# dummy.net
KiCad netlist of a schematic drawn in EAGLE
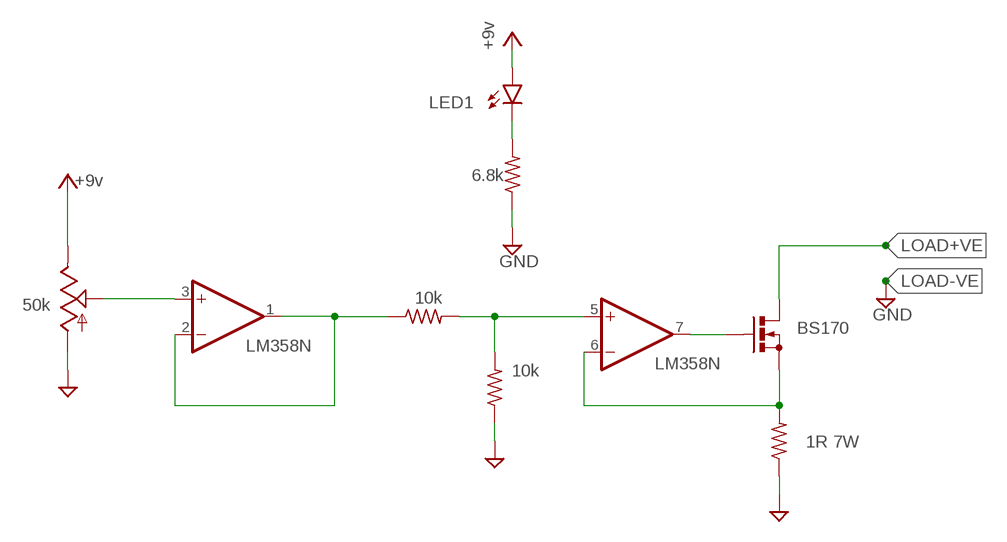
[diagram p0: schematic, sheet 1]

(export (version "E")
  (design (tool "Eeschema 10.0.6"))
  (components
    (comp (ref "IC1")
      (value "LM358N")
      (footprint "eagle-import:DIL08")
      (libsource (lib "eagle-import") (part "LM358N"))
    )
    (comp (ref "LED1")
      (value "LED5MM")
      (footprint "eagle-import:LED5MM")
      (libsource (lib "eagle-import") (part "LED5MM"))
    )
    (comp (ref "Q1")
      (value "BS170")
      (footprint "eagle-import:SOT54E")
      (libsource (lib "eagle-import") (part "BS170"))
    )
    (comp (ref "R1")
      (value "50k")
      (footprint "eagle-import:B25P")
      (libsource (lib "eagle-import") (part "TRIM_US-B25P"))
    )
    (comp (ref "R2")
      (value "10k")
      (footprint "eagle-import:0207_10")
      (libsource (lib "eagle-import") (part "R-US_0207/10"))
    )
    (comp (ref "R3")
      (value "10k")
      (footprint "eagle-import:0207_10")
      (libsource (lib "eagle-import") (part "R-US_0207/10"))
    )
    (comp (ref "R4")
      (value "1R 7W")
      (footprint "eagle-import:0207_10")
      (libsource (lib "eagle-import") (part "R-US_0207/10"))
    )
    (comp (ref "R5")
      (value "6.8k")
      (footprint "eagle-import:0207_10")
      (libsource (lib "eagle-import") (part "R-US_0207/10"))
    )
  )
  (nets
    (net (code "1") (name "+9v") (class "Default")
      (node (ref "LED1") (pin "A") (pinfunction "A_A") (pintype "passive"))
      (node (ref "R1") (pin "E") (pinfunction "E_E") (pintype "passive"))
    )
    (net (code "2") (name "LOAD+VE") (class "Default")
      (node (ref "Q1") (pin "D") (pinfunction "D_D") (pintype "passive"))
    )
    (net (code "3") (name "LOAD-VE") (class "Default")
      (node (ref "R1") (pin "A") (pinfunction "A_A") (pintype "passive"))
      (node (ref "R3") (pin "1") (pinfunction "1_1") (pintype "passive"))
      (node (ref "R4") (pin "1") (pinfunction "1_1") (pintype "passive"))
      (node (ref "R5") (pin "1") (pinfunction "1_1") (pintype "passive"))
    )
    (net (code "4") (name "Net-(IC1A-+IN)") (class "Default")
      (node (ref "IC1") (pin "3") (pinfunction "+IN_3") (pintype "input"))
      (node (ref "R1") (pin "S") (pinfunction "S_S") (pintype "passive"))
    )
    (net (code "5") (name "Net-(IC1A--IN)") (class "Default")
      (node (ref "IC1") (pin "1") (pinfunction "OUT_1") (pintype "output"))
      (node (ref "IC1") (pin "2") (pinfunction "-IN_2") (pintype "input"))
      (node (ref "R2") (pin "1") (pinfunction "1_1") (pintype "passive"))
    )
    (net (code "6") (name "Net-(IC1B-+IN)") (class "Default")
      (node (ref "IC1") (pin "5") (pinfunction "+IN_5") (pintype "input"))
      (node (ref "R2") (pin "2") (pinfunction "2_2") (pintype "passive"))
      (node (ref "R3") (pin "2") (pinfunction "2_2") (pintype "passive"))
    )
    (net (code "7") (name "Net-(IC1B--IN)") (class "Default")
      (node (ref "IC1") (pin "6") (pinfunction "-IN_6") (pintype "input"))
      (node (ref "Q1") (pin "S") (pinfunction "S_S") (pintype "passive"))
      (node (ref "R4") (pin "2") (pinfunction "2_2") (pintype "passive"))
    )
    (net (code "8") (name "Net-(IC1B-OUT)") (class "Default")
      (node (ref "IC1") (pin "7") (pinfunction "OUT_7") (pintype "output"))
      (node (ref "Q1") (pin "G") (pinfunction "G_G") (pintype "passive"))
    )
    (net (code "9") (name "Net-(LED1-C)") (class "Default")
      (node (ref "LED1") (pin "K") (pinfunction "C_K") (pintype "passive"))
      (node (ref "R5") (pin "2") (pinfunction "2_2") (pintype "passive"))
    )
  )
)
